# X16-ESC-Adapter.net
KiCad netlist of a schematic drawn in EAGLE
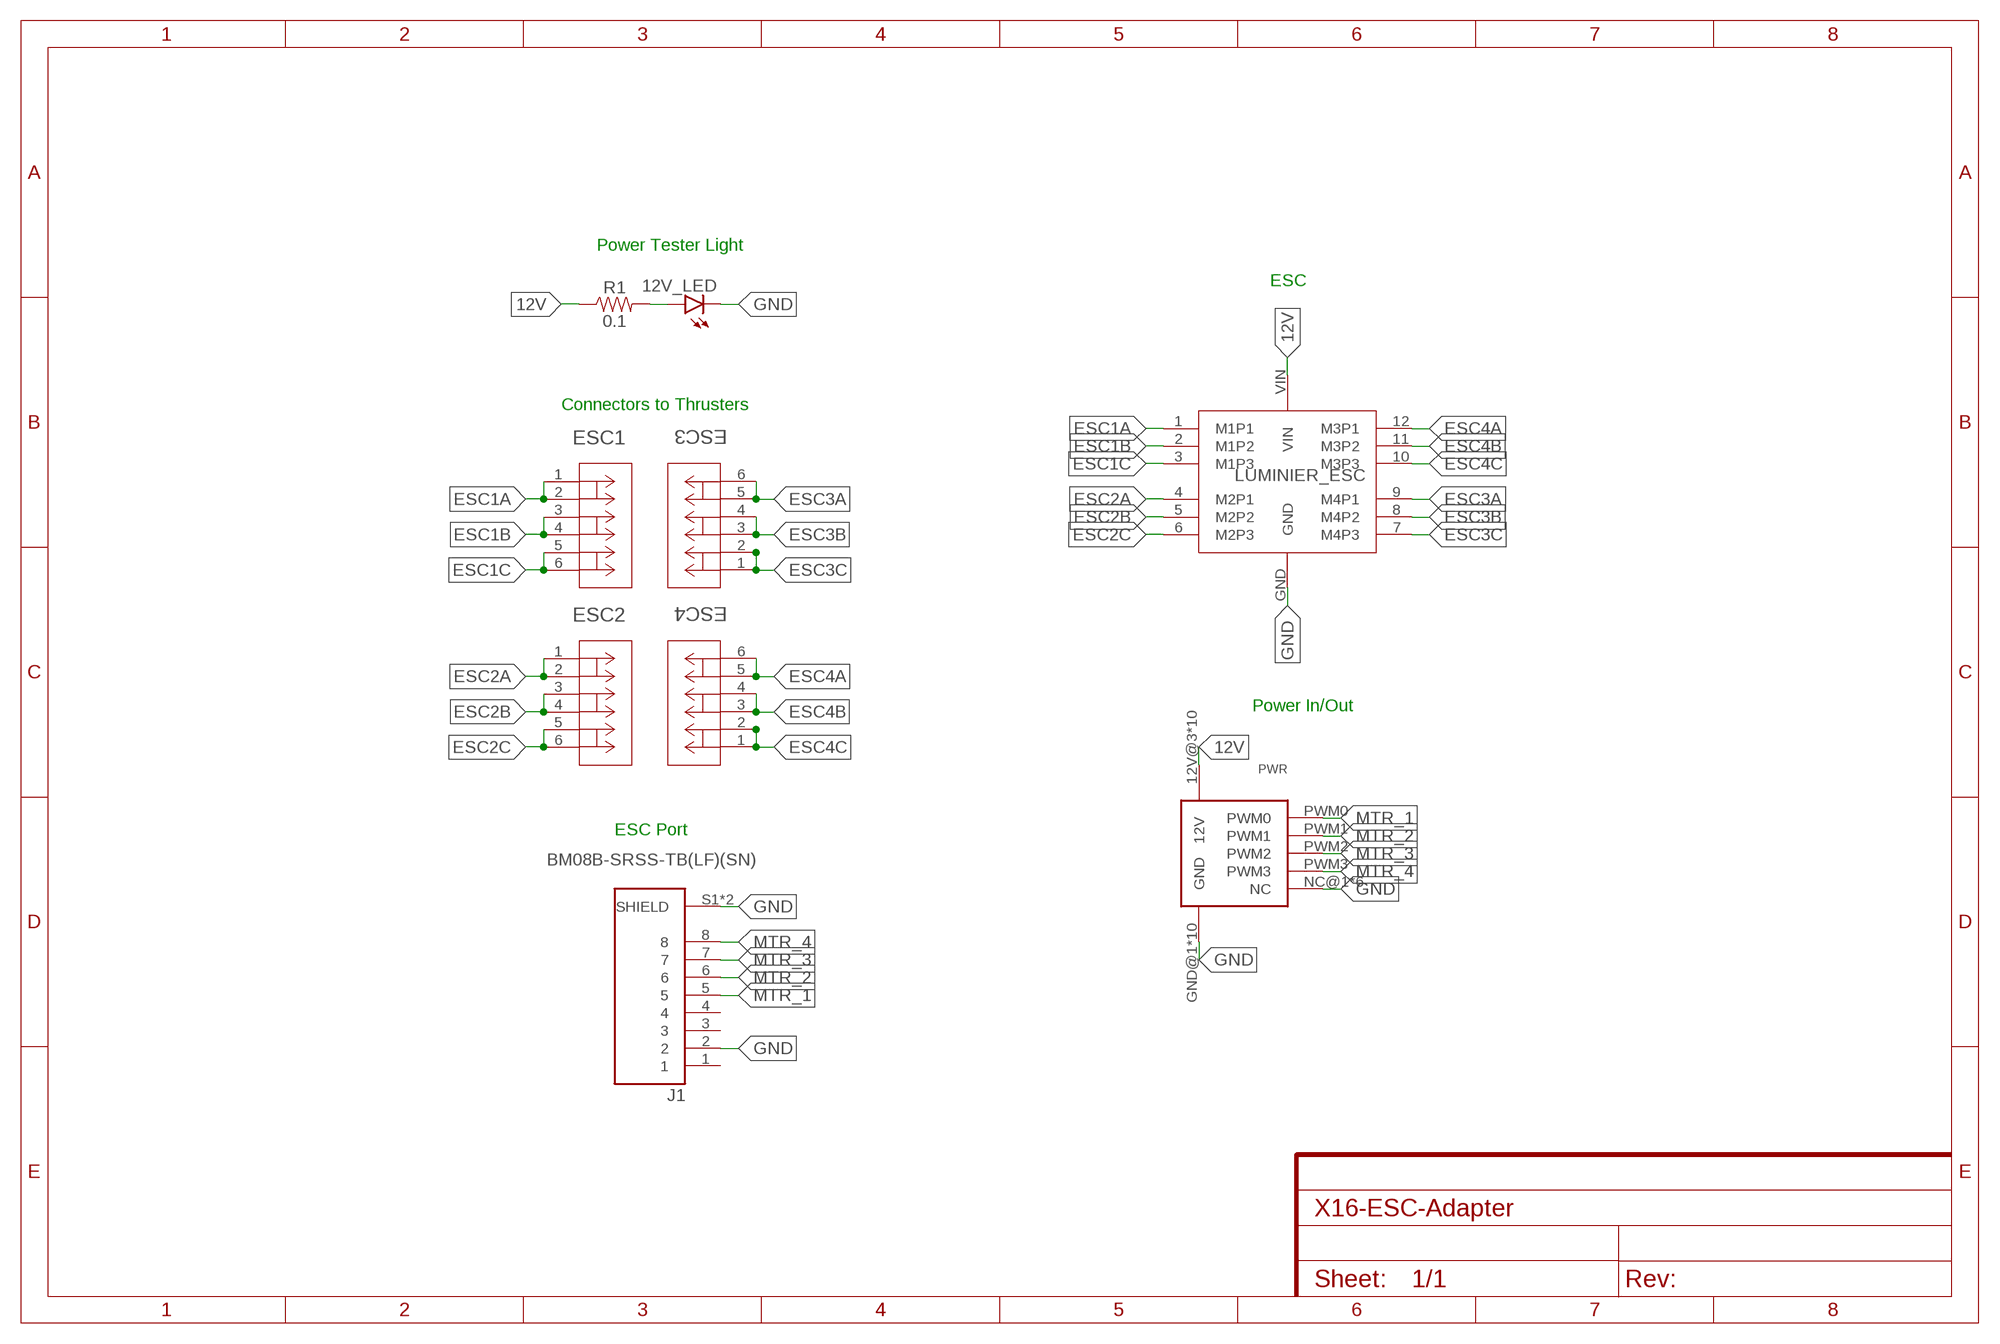
[diagram p0: schematic, sheet 1]

(export (version "E")
  (design (tool "Eeschema 10.0.6"))
  (components
    (comp (ref "12V_LED")
      (value "LEDCHIPLED_0805")
      (footprint "eagle-import:CHIPLED_0805")
      (libsource (lib "eagle-import") (part "LEDCHIPLED_0805"))
    )
    (comp (ref "ESC1")
      (value "CONN_1824750000")
      (footprint "eagle-import:CONN3_1824750000_WED")
      (fields
        (field (name "MANUFACTURER_PART_NUMBER") "1824750000")
        (field (name "COPYRIGHT") "Copyright (C) 2023 Ultra Librarian. All rights reserved.")
      )
      (libsource (lib "eagle-import") (part "CONN_1824750000"))
    )
    (comp (ref "ESC2")
      (value "CONN_1824750000")
      (footprint "eagle-import:CONN3_1824750000_WED")
      (fields
        (field (name "MANUFACTURER_PART_NUMBER") "1824750000")
        (field (name "COPYRIGHT") "Copyright (C) 2023 Ultra Librarian. All rights reserved.")
      )
      (libsource (lib "eagle-import") (part "CONN_1824750000"))
    )
    (comp (ref "ESC3")
      (value "CONN_1824750000")
      (footprint "eagle-import:CONN3_1824750000_WED")
      (fields
        (field (name "MANUFACTURER_PART_NUMBER") "1824750000")
        (field (name "COPYRIGHT") "Copyright (C) 2023 Ultra Librarian. All rights reserved.")
      )
      (libsource (lib "eagle-import") (part "CONN_1824750000"))
    )
    (comp (ref "ESC4")
      (value "CONN_1824750000")
      (footprint "eagle-import:CONN3_1824750000_WED")
      (fields
        (field (name "MANUFACTURER_PART_NUMBER") "1824750000")
        (field (name "COPYRIGHT") "Copyright (C) 2023 Ultra Librarian. All rights reserved.")
      )
      (libsource (lib "eagle-import") (part "CONN_1824750000"))
    )
    (comp (ref "J1")
      (value "BM08B-SRSS-TB(LF)(SN)")
      (footprint "eagle-import:JST_BM08B-SRSS-TB(LF)(SN)")
      (fields (field (name "MANUFACTURER") "JST Sales America Inc."))
      (libsource (lib "eagle-import") (part "BM08B-SRSS-TB(LF)(SN)"))
    )
    (comp (ref "LUMINIER_ESC")
      (value "LUMENIER")
      (footprint "eagle-import:LUMENIER")
      (libsource (lib "eagle-import") (part "LUMENIER"))
    )
    (comp (ref "PWR")
      (value "CONN_BACKPLANE_ESC_ADAPTER")
      (footprint "eagle-import:CONN_BACKPLANE_ESC_ADAPTER")
      (libsource (lib "eagle-import") (part "CONN_BACKPLANE_ESC_ADAPTER"))
    )
    (comp (ref "R1")
      (value "0.1")
      (footprint "eagle-import:0603")
      (libsource (lib "eagle-import") (part "0.1OHM-0603-1/3W-1%"))
    )
  )
  (nets
    (net (code "1") (name "12V") (class "Default")
      (node (ref "LUMINIER_ESC") (pin "VIN") (pinfunction "VIN_VIN") (pintype "bidirectional"))
      (node (ref "PWR") (pin "12V@10") (pinfunction "12V_12V@10") (pintype "bidirectional"))
      (node (ref "PWR") (pin "12V@11") (pinfunction "12V_12V@11") (pintype "bidirectional"))
      (node (ref "PWR") (pin "12V@12") (pinfunction "12V_12V@12") (pintype "bidirectional"))
      (node (ref "PWR") (pin "12V@3") (pinfunction "12V_12V@3") (pintype "bidirectional"))
      (node (ref "PWR") (pin "12V@4") (pinfunction "12V_12V@4") (pintype "bidirectional"))
      (node (ref "PWR") (pin "12V@5") (pinfunction "12V_12V@5") (pintype "bidirectional"))
      (node (ref "PWR") (pin "12V@6") (pinfunction "12V_12V@6") (pintype "bidirectional"))
      (node (ref "PWR") (pin "12V@7") (pinfunction "12V_12V@7") (pintype "bidirectional"))
      (node (ref "PWR") (pin "12V@8") (pinfunction "12V_12V@8") (pintype "bidirectional"))
      (node (ref "PWR") (pin "12V@9") (pinfunction "12V_12V@9") (pintype "bidirectional"))
      (node (ref "R1") (pin "1") (pinfunction "1_1") (pintype "passive"))
    )
    (net (code "2") (name "ESC1A") (class "Default")
      (node (ref "ESC1") (pin "1") (pinfunction "1_1") (pintype "passive"))
      (node (ref "ESC1") (pin "2") (pinfunction "2_2") (pintype "passive"))
      (node (ref "LUMINIER_ESC") (pin "1") (pinfunction "M1P1_1") (pintype "bidirectional"))
    )
    (net (code "3") (name "ESC1B") (class "Default")
      (node (ref "ESC1") (pin "3") (pinfunction "3_3") (pintype "passive"))
      (node (ref "ESC1") (pin "4") (pinfunction "4_4") (pintype "passive"))
      (node (ref "LUMINIER_ESC") (pin "2") (pinfunction "M1P2_2") (pintype "bidirectional"))
    )
    (net (code "4") (name "ESC1C") (class "Default")
      (node (ref "ESC1") (pin "5") (pinfunction "5_5") (pintype "passive"))
      (node (ref "ESC1") (pin "6") (pinfunction "6_6") (pintype "passive"))
      (node (ref "LUMINIER_ESC") (pin "3") (pinfunction "M1P3_3") (pintype "bidirectional"))
    )
    (net (code "5") (name "ESC2A") (class "Default")
      (node (ref "ESC2") (pin "1") (pinfunction "1_1") (pintype "passive"))
      (node (ref "ESC2") (pin "2") (pinfunction "2_2") (pintype "passive"))
      (node (ref "LUMINIER_ESC") (pin "4") (pinfunction "M2P1_4") (pintype "bidirectional"))
    )
    (net (code "6") (name "ESC2B") (class "Default")
      (node (ref "ESC2") (pin "3") (pinfunction "3_3") (pintype "passive"))
      (node (ref "ESC2") (pin "4") (pinfunction "4_4") (pintype "passive"))
      (node (ref "LUMINIER_ESC") (pin "5") (pinfunction "M2P2_5") (pintype "bidirectional"))
    )
    (net (code "7") (name "ESC2C") (class "Default")
      (node (ref "ESC2") (pin "5") (pinfunction "5_5") (pintype "passive"))
      (node (ref "ESC2") (pin "6") (pinfunction "6_6") (pintype "passive"))
      (node (ref "LUMINIER_ESC") (pin "6") (pinfunction "M2P3_6") (pintype "bidirectional"))
    )
    (net (code "8") (name "ESC3A") (class "Default")
      (node (ref "ESC3") (pin "5") (pinfunction "5_5") (pintype "passive"))
      (node (ref "ESC3") (pin "6") (pinfunction "6_6") (pintype "passive"))
      (node (ref "LUMINIER_ESC") (pin "9") (pinfunction "M4P1_9") (pintype "bidirectional"))
    )
    (net (code "9") (name "ESC3B") (class "Default")
      (node (ref "ESC3") (pin "3") (pinfunction "3_3") (pintype "passive"))
      (node (ref "ESC3") (pin "4") (pinfunction "4_4") (pintype "passive"))
      (node (ref "LUMINIER_ESC") (pin "8") (pinfunction "M4P2_8") (pintype "bidirectional"))
    )
    (net (code "10") (name "ESC3C") (class "Default")
      (node (ref "ESC3") (pin "1") (pinfunction "1_1") (pintype "passive"))
      (node (ref "ESC3") (pin "2") (pinfunction "2_2") (pintype "passive"))
      (node (ref "LUMINIER_ESC") (pin "7") (pinfunction "M4P3_7") (pintype "bidirectional"))
    )
    (net (code "11") (name "ESC4A") (class "Default")
      (node (ref "ESC4") (pin "5") (pinfunction "5_5") (pintype "passive"))
      (node (ref "ESC4") (pin "6") (pinfunction "6_6") (pintype "passive"))
      (node (ref "LUMINIER_ESC") (pin "12") (pinfunction "M3P1_12") (pintype "bidirectional"))
    )
    (net (code "12") (name "ESC4B") (class "Default")
      (node (ref "ESC4") (pin "3") (pinfunction "3_3") (pintype "passive"))
      (node (ref "ESC4") (pin "4") (pinfunction "4_4") (pintype "passive"))
      (node (ref "LUMINIER_ESC") (pin "11") (pinfunction "M3P2_11") (pintype "bidirectional"))
    )
    (net (code "13") (name "ESC4C") (class "Default")
      (node (ref "ESC4") (pin "1") (pinfunction "1_1") (pintype "passive"))
      (node (ref "ESC4") (pin "2") (pinfunction "2_2") (pintype "passive"))
      (node (ref "LUMINIER_ESC") (pin "10") (pinfunction "M3P3_10") (pintype "bidirectional"))
    )
    (net (code "14") (name "GND") (class "Default")
      (node (ref "12V_LED") (pin "C") (pinfunction "C_C") (pintype "passive"))
      (node (ref "J1") (pin "2") (pinfunction "2_2") (pintype "passive"))
      (node (ref "J1") (pin "S1") (pinfunction "SHIELD_S1") (pintype "passive"))
      (node (ref "J1") (pin "S2") (pinfunction "SHIELD_S2") (pintype "passive"))
      (node (ref "LUMINIER_ESC") (pin "GND") (pinfunction "GND_GND") (pintype "bidirectional"))
      (node (ref "PWR") (pin "GND@1") (pinfunction "GND_GND@1") (pintype "bidirectional"))
      (node (ref "PWR") (pin "GND@10") (pinfunction "GND_GND@10") (pintype "bidirectional"))
      (node (ref "PWR") (pin "GND@2") (pinfunction "GND_GND@2") (pintype "bidirectional"))
      (node (ref "PWR") (pin "GND@3") (pinfunction "GND_GND@3") (pintype "bidirectional"))
      (node (ref "PWR") (pin "GND@4") (pinfunction "GND_GND@4") (pintype "bidirectional"))
      (node (ref "PWR") (pin "GND@5") (pinfunction "GND_GND@5") (pintype "bidirectional"))
      (node (ref "PWR") (pin "GND@6") (pinfunction "GND_GND@6") (pintype "bidirectional"))
      (node (ref "PWR") (pin "GND@7") (pinfunction "GND_GND@7") (pintype "bidirectional"))
      (node (ref "PWR") (pin "GND@8") (pinfunction "GND_GND@8") (pintype "bidirectional"))
      (node (ref "PWR") (pin "GND@9") (pinfunction "GND_GND@9") (pintype "bidirectional"))
      (node (ref "PWR") (pin "NC@1") (pinfunction "NC_NC@1") (pintype "bidirectional"))
      (node (ref "PWR") (pin "NC@2") (pinfunction "NC_NC@2") (pintype "bidirectional"))
      (node (ref "PWR") (pin "NC@3") (pinfunction "NC_NC@3") (pintype "bidirectional"))
      (node (ref "PWR") (pin "NC@4") (pinfunction "NC_NC@4") (pintype "bidirectional"))
      (node (ref "PWR") (pin "NC@5") (pinfunction "NC_NC@5") (pintype "bidirectional"))
      (node (ref "PWR") (pin "NC@6") (pinfunction "NC_NC@6") (pintype "bidirectional"))
    )
    (net (code "15") (name "MTR_1") (class "Default")
      (node (ref "J1") (pin "5") (pinfunction "5_5") (pintype "passive"))
      (node (ref "PWR") (pin "PWM0") (pinfunction "PWM0_PWM0") (pintype "bidirectional"))
    )
    (net (code "16") (name "MTR_2") (class "Default")
      (node (ref "J1") (pin "6") (pinfunction "6_6") (pintype "passive"))
      (node (ref "PWR") (pin "PWM1") (pinfunction "PWM1_PWM1") (pintype "bidirectional"))
    )
    (net (code "17") (name "MTR_3") (class "Default")
      (node (ref "J1") (pin "7") (pinfunction "7_7") (pintype "passive"))
      (node (ref "PWR") (pin "PWM2") (pinfunction "PWM2_PWM2") (pintype "bidirectional"))
    )
    (net (code "18") (name "MTR_4") (class "Default")
      (node (ref "J1") (pin "8") (pinfunction "8_8") (pintype "passive"))
      (node (ref "PWR") (pin "PWM3") (pinfunction "PWM3_PWM3") (pintype "bidirectional"))
    )
    (net (code "19") (name "Net-(12V_LED-PadA)") (class "Default")
      (node (ref "12V_LED") (pin "A") (pinfunction "A_A") (pintype "passive"))
      (node (ref "R1") (pin "2") (pinfunction "2_2") (pintype "passive"))
    )
    (net (code "20") (name "unconnected-(J1-Pad1)") (class "Default")
      (node (ref "J1") (pin "1") (pinfunction "1_1") (pintype "passive"))
    )
    (net (code "21") (name "unconnected-(J1-Pad3)") (class "Default")
      (node (ref "J1") (pin "3") (pinfunction "3_3") (pintype "passive"))
    )
    (net (code "22") (name "unconnected-(J1-Pad4)") (class "Default")
      (node (ref "J1") (pin "4") (pinfunction "4_4") (pintype "passive"))
    )
  )
)
